# bicyclelab-charger.net
KiCad netlist of a schematic drawn in EAGLE
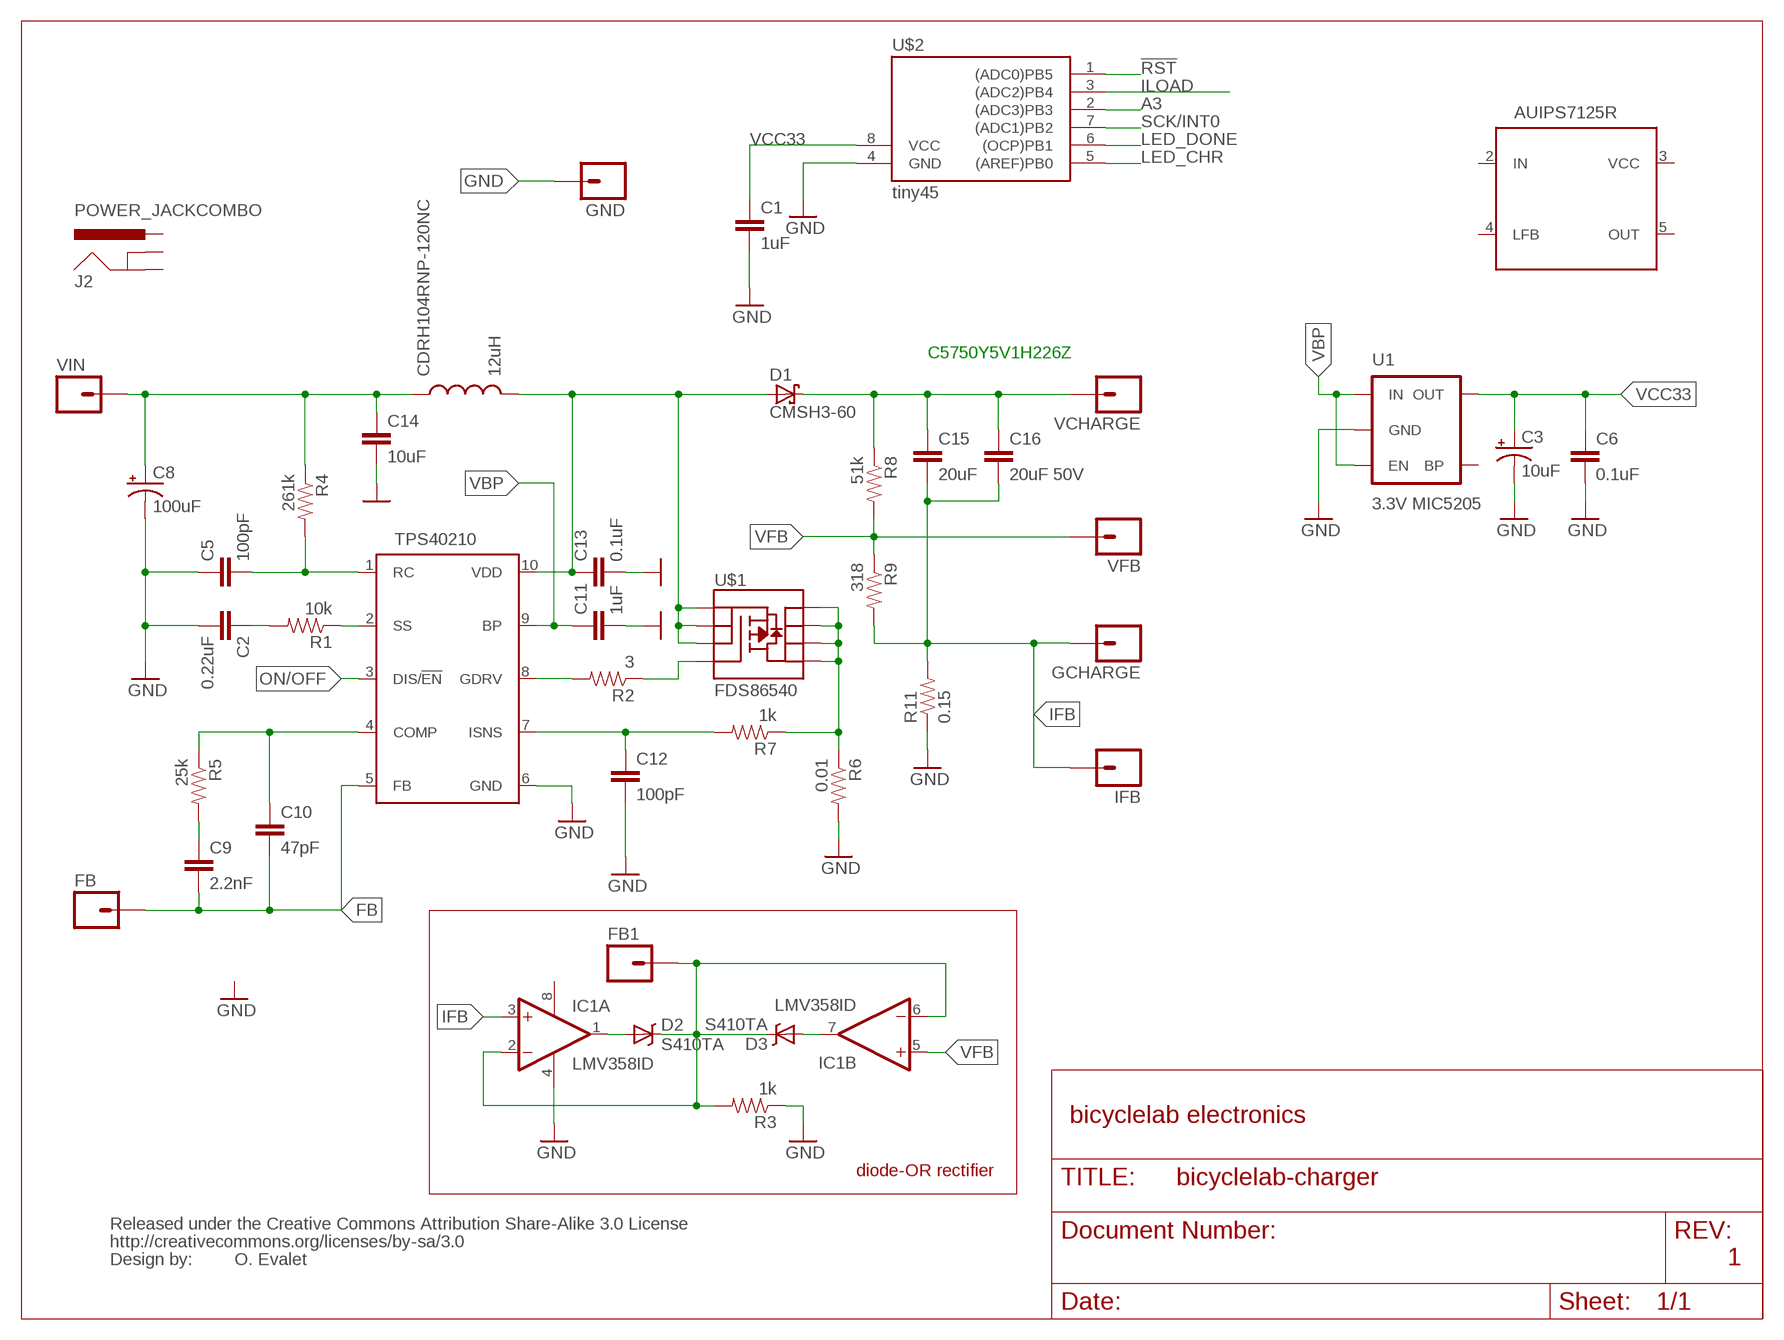
[diagram p0: schematic, sheet 1]

(export (version "E")
  (design (tool "Eeschema 10.0.6"))
  (components
    (comp (ref "11")
      (value "TPS40211")
      (footprint "eagle-import:MSOP-10-GNDPAD")
      (libsource (lib "eagle-import") (part "TPS40210"))
    )
    (comp (ref "C1")
      (value "1uF")
      (footprint "eagle-import:0402-CAP")
      (libsource (lib "eagle-import") (part "SparkFun_CAP0402-CAP"))
    )
    (comp (ref "C2")
      (value "0.22uF")
      (footprint "eagle-import:0402-CAP")
      (libsource (lib "eagle-import") (part "SparkFun_CAP0402-CAP"))
    )
    (comp (ref "C3")
      (value "10uF")
      (footprint "eagle-import:EIA3216")
      (libsource (lib "eagle-import") (part "SparkFun_CAP_POL1206"))
    )
    (comp (ref "C5")
      (value "100pF")
      (footprint "eagle-import:0402-CAP")
      (libsource (lib "eagle-import") (part "SparkFun_CAP0402-CAP"))
    )
    (comp (ref "C6")
      (value "0.1uF")
      (footprint "eagle-import:0603-CAP")
      (libsource (lib "eagle-import") (part "SparkFun_CAP0603-CAP"))
    )
    (comp (ref "C8")
      (value "100uF")
      (footprint "eagle-import:PANASONIC_C")
      (libsource (lib "eagle-import") (part "CAP_POLC"))
    )
    (comp (ref "C9")
      (value "2.2nF")
      (footprint "eagle-import:0402-CAP")
      (libsource (lib "eagle-import") (part "SparkFun_CAP0402-CAP"))
    )
    (comp (ref "C10")
      (value "47pF")
      (footprint "eagle-import:0402-CAP")
      (libsource (lib "eagle-import") (part "SparkFun_CAP0402-CAP"))
    )
    (comp (ref "C11")
      (value "1uF")
      (footprint "eagle-import:0402-CAP")
      (libsource (lib "eagle-import") (part "SparkFun_CAP0402-CAP"))
    )
    (comp (ref "C12")
      (value "100pF")
      (footprint "eagle-import:0402-CAP")
      (libsource (lib "eagle-import") (part "SparkFun_CAP0402-CAP"))
    )
    (comp (ref "C13")
      (value "0.1uF")
      (footprint "eagle-import:0402-CAP")
      (libsource (lib "eagle-import") (part "SparkFun_CAP0402-CAP"))
    )
    (comp (ref "C14")
      (value "10uF")
      (footprint "eagle-import:1206")
      (libsource (lib "eagle-import") (part "CAP1206"))
    )
    (comp (ref "C15")
      (value "20uF")
      (footprint "eagle-import:C2220K")
      (libsource (lib "eagle-import") (part "CAPCAP2220"))
    )
    (comp (ref "C16")
      (value "20uF 50V")
      (footprint "eagle-import:C2220K")
      (libsource (lib "eagle-import") (part "CAPCAP2220"))
    )
    (comp (ref "CDRH104RNP-120NC")
      (value "12uH")
      (footprint "eagle-import:CR75")
      (libsource (lib "eagle-import") (part "INDUCTORCR75"))
    )
    (comp (ref "D1")
      (value "CMSH3-60")
      (footprint "eagle-import:SMC")
      (libsource (lib "eagle-import") (part "MBRS30T32"))
    )
    (comp (ref "D2")
      (value "S410TA")
      (footprint "eagle-import:SOD-323")
      (libsource (lib "eagle-import") (part "DIODE-SCHOTTKY"))
    )
    (comp (ref "D3")
      (value "S410TA")
      (footprint "eagle-import:SOD-323")
      (libsource (lib "eagle-import") (part "DIODE-SCHOTTKY"))
    )
    (comp (ref "FB")
      (value "M01SMDNS")
      (footprint "eagle-import:1X01NS")
      (libsource (lib "eagle-import") (part "M01SMDNS"))
    )
    (comp (ref "FB1")
      (value "M01SMDNS")
      (footprint "eagle-import:1X01NS")
      (libsource (lib "eagle-import") (part "M01SMDNS"))
    )
    (comp (ref "GCHARGE")
      (value "M01SMDNS")
      (footprint "eagle-import:1X01NS")
      (libsource (lib "eagle-import") (part "M01SMDNS"))
    )
    (comp (ref "GND")
      (value "M01SMDNS")
      (footprint "eagle-import:1X01NS")
      (libsource (lib "eagle-import") (part "M01SMDNS"))
    )
    (comp (ref "IC1")
      (value "LMV358ID")
      (footprint "eagle-import:SO08")
      (libsource (lib "eagle-import") (part "MCP602SN"))
    )
    (comp (ref "IFB")
      (value "M01SMDNS")
      (footprint "eagle-import:1X01NS")
      (libsource (lib "eagle-import") (part "M01SMDNS"))
    )
    (comp (ref "J2")
      (value "POWER_JACKCOMBO")
      (footprint "eagle-import:POWER_JACK_COMBO")
      (libsource (lib "eagle-import") (part "POWER_JACKCOMBO"))
    )
    (comp (ref "R1")
      (value "10k")
      (footprint "eagle-import:0402-RES")
      (libsource (lib "eagle-import") (part "RESISTOR0402-RES"))
    )
    (comp (ref "R2")
      (value "3")
      (footprint "eagle-import:0402-RES")
      (libsource (lib "eagle-import") (part "RESISTOR0402-RES"))
    )
    (comp (ref "R3")
      (value "1k")
      (footprint "eagle-import:0402-RES")
      (libsource (lib "eagle-import") (part "RESISTOR0402-RES"))
    )
    (comp (ref "R4")
      (value "261k")
      (footprint "eagle-import:0402-RES")
      (libsource (lib "eagle-import") (part "RESISTOR0402-RES"))
    )
    (comp (ref "R5")
      (value "25k")
      (footprint "eagle-import:0402-RES")
      (libsource (lib "eagle-import") (part "RESISTOR0402-RES"))
    )
    (comp (ref "R6")
      (value "0.01")
      (footprint "eagle-import:0402-RES")
      (libsource (lib "eagle-import") (part "RESISTOR0402-RES"))
    )
    (comp (ref "R7")
      (value "1k")
      (footprint "eagle-import:0402-RES")
      (libsource (lib "eagle-import") (part "RESISTOR0402-RES"))
    )
    (comp (ref "R8")
      (value "51k")
      (footprint "eagle-import:0402-RES")
      (libsource (lib "eagle-import") (part "RESISTOR0402-RES"))
    )
    (comp (ref "R9")
      (value "318")
      (footprint "eagle-import:0402-RES")
      (libsource (lib "eagle-import") (part "RESISTOR0402-RES"))
    )
    (comp (ref "R11")
      (value "0.15")
      (footprint "eagle-import:0402-RES")
      (libsource (lib "eagle-import") (part "RESISTOR0402-RES"))
    )
    (comp (ref "U$1")
      (value "FDS86540")
      (footprint "eagle-import:SO08")
      (libsource (lib "eagle-import") (part "MOSFET-PCHANNEL-SOIC8SOIC8"))
    )
    (comp (ref "U$2")
      (value "tiny45")
      (footprint "eagle-import:SOIC8")
      (libsource (lib "eagle-import") (part "TINY25/45/85-20SU"))
    )
    (comp (ref "U$5")
      (value "CREATIVE_COMMONS")
      (footprint "eagle-import:CREATIVE_COMMONS")
      (libsource (lib "eagle-import") (part "CREATIVE_COMMONS"))
    )
    (comp (ref "U$8")
      (value "AUIPS7125R")
      (footprint "eagle-import:DPAK-5")
      (libsource (lib "eagle-import") (part "AUIPS7125R"))
    )
    (comp (ref "U1")
      (value "3.3V MIC5205")
      (footprint "eagle-import:SOT23-5")
      (libsource (lib "eagle-import") (part "V_REG_LDOSMD"))
    )
    (comp (ref "VCHARGE")
      (value "M01SMDNS")
      (footprint "eagle-import:1X01NS")
      (libsource (lib "eagle-import") (part "M01SMDNS"))
    )
    (comp (ref "VFB")
      (value "M01SMDNS")
      (footprint "eagle-import:1X01NS")
      (libsource (lib "eagle-import") (part "M01SMDNS"))
    )
    (comp (ref "VIN")
      (value "M01SMDNS")
      (footprint "eagle-import:1X01NS")
      (libsource (lib "eagle-import") (part "M01SMDNS"))
    )
  )
  (nets
    (net (code "1") (name "/A3") (class "Default")
      (node (ref "U$2") (pin "2") (pinfunction "(ADC3)PB3_2") (pintype "bidirectional"))
    )
    (net (code "2") (name "/ILOAD") (class "Default")
      (node (ref "U$2") (pin "3") (pinfunction "(ADC2)PB4_3") (pintype "bidirectional"))
    )
    (net (code "3") (name "/LED_CHR") (class "Default")
      (node (ref "U$2") (pin "5") (pinfunction "(AREF)PB0_5") (pintype "bidirectional"))
    )
    (net (code "4") (name "/LED_DONE") (class "Default")
      (node (ref "U$2") (pin "6") (pinfunction "(OCP)PB1_6") (pintype "bidirectional"))
    )
    (net (code "5") (name "/SCK{slash}INT0") (class "Default")
      (node (ref "U$2") (pin "7") (pinfunction "(ADC1)PB2_7") (pintype "bidirectional"))
    )
    (net (code "6") (name "/V+") (class "Default")
      (node (ref "IC1") (pin "8") (pinfunction "V+_8") (pintype "power_in"))
    )
    (net (code "7") (name "/~{RST}") (class "Default")
      (node (ref "U$2") (pin "1") (pinfunction "(ADC0)PB5_1") (pintype "bidirectional"))
    )
    (net (code "8") (name "FB") (class "Default")
      (node (ref "11") (pin "5") (pinfunction "FB_5") (pintype "input"))
      (node (ref "C10") (pin "2") (pinfunction "2_2") (pintype "passive"))
      (node (ref "C9") (pin "2") (pinfunction "2_2") (pintype "passive"))
      (node (ref "FB") (pin "1") (pinfunction "1_1") (pintype "passive"))
    )
    (net (code "9") (name "GND") (class "Default")
      (node (ref "11") (pin "6") (pinfunction "GND_6") (pintype "passive"))
      (node (ref "C1") (pin "2") (pinfunction "2_2") (pintype "passive"))
      (node (ref "C11") (pin "2") (pinfunction "2_2") (pintype "passive"))
      (node (ref "C12") (pin "2") (pinfunction "2_2") (pintype "passive"))
      (node (ref "C13") (pin "2") (pinfunction "2_2") (pintype "passive"))
      (node (ref "C14") (pin "2") (pinfunction "2_2") (pintype "passive"))
      (node (ref "C2") (pin "2") (pinfunction "2_2") (pintype "passive"))
      (node (ref "C3") (pin "C") (pinfunction "-_C") (pintype "passive"))
      (node (ref "C5") (pin "1") (pinfunction "1_1") (pintype "passive"))
      (node (ref "C6") (pin "2") (pinfunction "2_2") (pintype "passive"))
      (node (ref "C8") (pin "-") (pinfunction "-_-") (pintype "passive"))
      (node (ref "GND") (pin "1") (pinfunction "1_1") (pintype "passive"))
      (node (ref "IC1") (pin "4") (pinfunction "V-_4") (pintype "power_in"))
      (node (ref "R11") (pin "1") (pinfunction "1_1") (pintype "passive"))
      (node (ref "R3") (pin "1") (pinfunction "1_1") (pintype "passive"))
      (node (ref "R6") (pin "2") (pinfunction "2_2") (pintype "passive"))
      (node (ref "U$2") (pin "4") (pinfunction "GND_4") (pintype "power_in"))
      (node (ref "U1") (pin "2") (pinfunction "GND_2") (pintype "input"))
    )
    (net (code "10") (name "IFB") (class "Default")
      (node (ref "C15") (pin "2") (pinfunction "2_2") (pintype "passive"))
      (node (ref "C16") (pin "2") (pinfunction "2_2") (pintype "passive"))
      (node (ref "GCHARGE") (pin "1") (pinfunction "1_1") (pintype "passive"))
      (node (ref "IC1") (pin "3") (pinfunction "+IN_3") (pintype "input"))
      (node (ref "IFB") (pin "1") (pinfunction "1_1") (pintype "passive"))
      (node (ref "R11") (pin "2") (pinfunction "2_2") (pintype "passive"))
      (node (ref "R9") (pin "2") (pinfunction "2_2") (pintype "passive"))
    )
    (net (code "11") (name "Net-(11-COMP)") (class "Default")
      (node (ref "11") (pin "4") (pinfunction "COMP_4") (pintype "input"))
      (node (ref "C10") (pin "1") (pinfunction "1_1") (pintype "passive"))
      (node (ref "R5") (pin "1") (pinfunction "1_1") (pintype "passive"))
    )
    (net (code "12") (name "Net-(11-GDRV)") (class "Default")
      (node (ref "11") (pin "8") (pinfunction "GDRV_8") (pintype "passive"))
      (node (ref "R2") (pin "2") (pinfunction "2_2") (pintype "passive"))
    )
    (net (code "13") (name "Net-(11-ISNS)") (class "Default")
      (node (ref "11") (pin "7") (pinfunction "ISNS_7") (pintype "passive"))
      (node (ref "C12") (pin "1") (pinfunction "1_1") (pintype "passive"))
      (node (ref "R7") (pin "2") (pinfunction "2_2") (pintype "passive"))
    )
    (net (code "14") (name "Net-(11-RC)") (class "Default")
      (node (ref "11") (pin "1") (pinfunction "RC_1") (pintype "input"))
      (node (ref "C5") (pin "2") (pinfunction "2_2") (pintype "passive"))
      (node (ref "R4") (pin "2") (pinfunction "2_2") (pintype "passive"))
    )
    (net (code "15") (name "Net-(11-SS)") (class "Default")
      (node (ref "11") (pin "2") (pinfunction "SS_2") (pintype "input"))
      (node (ref "R1") (pin "1") (pinfunction "1_1") (pintype "passive"))
    )
    (net (code "16") (name "Net-(11-VDD)") (class "Default")
      (node (ref "11") (pin "10") (pinfunction "VDD_10") (pintype "passive"))
      (node (ref "C13") (pin "1") (pinfunction "1_1") (pintype "passive"))
      (node (ref "CDRH104RNP-120NC") (pin "P$2") (pinfunction "2_P$2") (pintype "passive"))
      (node (ref "D1") (pin "A") (pinfunction "A_A") (pintype "passive"))
      (node (ref "U$1") (pin "1") (pinfunction "S_1") (pintype "bidirectional"))
      (node (ref "U$1") (pin "2") (pinfunction "S_2") (pintype "bidirectional"))
      (node (ref "U$1") (pin "3") (pinfunction "S_3") (pintype "bidirectional"))
    )
    (net (code "17") (name "Net-(C2-Pad1)") (class "Default")
      (node (ref "C2") (pin "1") (pinfunction "1_1") (pintype "passive"))
      (node (ref "R1") (pin "2") (pinfunction "2_2") (pintype "passive"))
    )
    (net (code "18") (name "Net-(C9-Pad1)") (class "Default")
      (node (ref "C9") (pin "1") (pinfunction "1_1") (pintype "passive"))
      (node (ref "R5") (pin "2") (pinfunction "2_2") (pintype "passive"))
    )
    (net (code "19") (name "Net-(C15-Pad1)") (class "Default")
      (node (ref "C15") (pin "1") (pinfunction "1_1") (pintype "passive"))
      (node (ref "C16") (pin "1") (pinfunction "1_1") (pintype "passive"))
      (node (ref "D1") (pin "C") (pinfunction "C_C") (pintype "passive"))
      (node (ref "R8") (pin "1") (pinfunction "1_1") (pintype "passive"))
      (node (ref "VCHARGE") (pin "1") (pinfunction "1_1") (pintype "passive"))
    )
    (net (code "20") (name "Net-(CDRH104RNP-120NC-1)") (class "Default")
      (node (ref "C14") (pin "1") (pinfunction "1_1") (pintype "passive"))
      (node (ref "C8") (pin "+") (pinfunction "+_+") (pintype "passive"))
      (node (ref "CDRH104RNP-120NC") (pin "P$1") (pinfunction "1_P$1") (pintype "passive"))
      (node (ref "R4") (pin "1") (pinfunction "1_1") (pintype "passive"))
      (node (ref "VIN") (pin "1") (pinfunction "1_1") (pintype "passive"))
    )
    (net (code "21") (name "Net-(D2-A)") (class "Default")
      (node (ref "D2") (pin "2") (pinfunction "A_2") (pintype "passive"))
      (node (ref "IC1") (pin "1") (pinfunction "OUT_1") (pintype "output"))
    )
    (net (code "22") (name "Net-(D2-C)") (class "Default")
      (node (ref "D2") (pin "1") (pinfunction "C_1") (pintype "passive"))
      (node (ref "D3") (pin "1") (pinfunction "C_1") (pintype "passive"))
      (node (ref "FB1") (pin "1") (pinfunction "1_1") (pintype "passive"))
      (node (ref "IC1") (pin "2") (pinfunction "-IN_2") (pintype "input"))
      (node (ref "IC1") (pin "6") (pinfunction "-IN_6") (pintype "input"))
      (node (ref "R3") (pin "2") (pinfunction "2_2") (pintype "passive"))
    )
    (net (code "23") (name "Net-(D3-A)") (class "Default")
      (node (ref "D3") (pin "2") (pinfunction "A_2") (pintype "passive"))
      (node (ref "IC1") (pin "7") (pinfunction "OUT_7") (pintype "output"))
    )
    (net (code "24") (name "Net-(R6-Pad1)") (class "Default")
      (node (ref "R6") (pin "1") (pinfunction "1_1") (pintype "passive"))
      (node (ref "R7") (pin "1") (pinfunction "1_1") (pintype "passive"))
      (node (ref "U$1") (pin "5") (pinfunction "D_5") (pintype "bidirectional"))
      (node (ref "U$1") (pin "6") (pinfunction "D_6") (pintype "bidirectional"))
      (node (ref "U$1") (pin "7") (pinfunction "D_7") (pintype "bidirectional"))
      (node (ref "U$1") (pin "8") (pinfunction "D_8") (pintype "bidirectional"))
    )
    (net (code "25") (name "Net-(U$1-G)") (class "Default")
      (node (ref "R2") (pin "1") (pinfunction "1_1") (pintype "passive"))
      (node (ref "U$1") (pin "4") (pinfunction "G_4") (pintype "bidirectional"))
    )
    (net (code "26") (name "ON{slash}OFF") (class "Default")
      (node (ref "11") (pin "3") (pinfunction "DIS/~{EN}_3") (pintype "input"))
    )
    (net (code "27") (name "VBP") (class "Default")
      (node (ref "11") (pin "9") (pinfunction "BP_9") (pintype "passive"))
      (node (ref "C11") (pin "1") (pinfunction "1_1") (pintype "passive"))
      (node (ref "U1") (pin "1") (pinfunction "IN_1") (pintype "input"))
      (node (ref "U1") (pin "3") (pinfunction "EN_3") (pintype "input"))
    )
    (net (code "28") (name "VCC33") (class "Default")
      (node (ref "C1") (pin "1") (pinfunction "1_1") (pintype "passive"))
      (node (ref "C3") (pin "A") (pinfunction "+_A") (pintype "passive"))
      (node (ref "C6") (pin "1") (pinfunction "1_1") (pintype "passive"))
      (node (ref "U$2") (pin "8") (pinfunction "VCC_8") (pintype "power_in"))
      (node (ref "U1") (pin "5") (pinfunction "OUT_5") (pintype "passive"))
    )
    (net (code "29") (name "VFB") (class "Default")
      (node (ref "IC1") (pin "5") (pinfunction "+IN_5") (pintype "input"))
      (node (ref "R8") (pin "2") (pinfunction "2_2") (pintype "passive"))
      (node (ref "R9") (pin "1") (pinfunction "1_1") (pintype "passive"))
      (node (ref "VFB") (pin "1") (pinfunction "1_1") (pintype "passive"))
    )
    (net (code "30") (name "unconnected-(11-PadGND)") (class "Default")
      (node (ref "11") (pin "GND") (pinfunction "GND_GND") (pintype "passive"))
    )
    (net (code "31") (name "unconnected-(J2-GND-PadGND@1)") (class "Default")
      (node (ref "J2") (pin "GND@1") (pinfunction "GND_GND@1") (pintype "bidirectional"))
    )
    (net (code "32") (name "unconnected-(J2-GNDBREAK-PadGND)") (class "Default")
      (node (ref "J2") (pin "GND") (pinfunction "GNDBREAK_GND") (pintype "bidirectional"))
    )
    (net (code "33") (name "unconnected-(J2-PWR-PadPOWER)") (class "Default")
      (node (ref "J2") (pin "POWER") (pinfunction "PWR_POWER") (pintype "bidirectional"))
    )
    (net (code "34") (name "unconnected-(U$8-IN-Pad2)") (class "Default")
      (node (ref "U$8") (pin "2") (pinfunction "IN_2") (pintype "input"))
    )
    (net (code "35") (name "unconnected-(U$8-LFB-Pad4)") (class "Default")
      (node (ref "U$8") (pin "4") (pinfunction "LFB_4") (pintype "output"))
    )
    (net (code "36") (name "unconnected-(U$8-NC-Pad1)") (class "Default")
      (node (ref "U$8") (pin "1") (pinfunction "NC_1") (pintype "no_connect"))
    )
    (net (code "37") (name "unconnected-(U$8-OUT-Pad5)") (class "Default")
      (node (ref "U$8") (pin "5") (pinfunction "OUT_5") (pintype "output"))
    )
    (net (code "38") (name "unconnected-(U$8-VCC-Pad3)") (class "Default")
      (node (ref "U$8") (pin "3") (pinfunction "VCC_3") (pintype "input"))
    )
    (net (code "39") (name "unconnected-(U1-BP-Pad4)") (class "Default")
      (node (ref "U1") (pin "4") (pinfunction "BP_4") (pintype "input"))
    )
  )
)
